# extension.net
KiCad netlist of a schematic drawn in Altium Designer
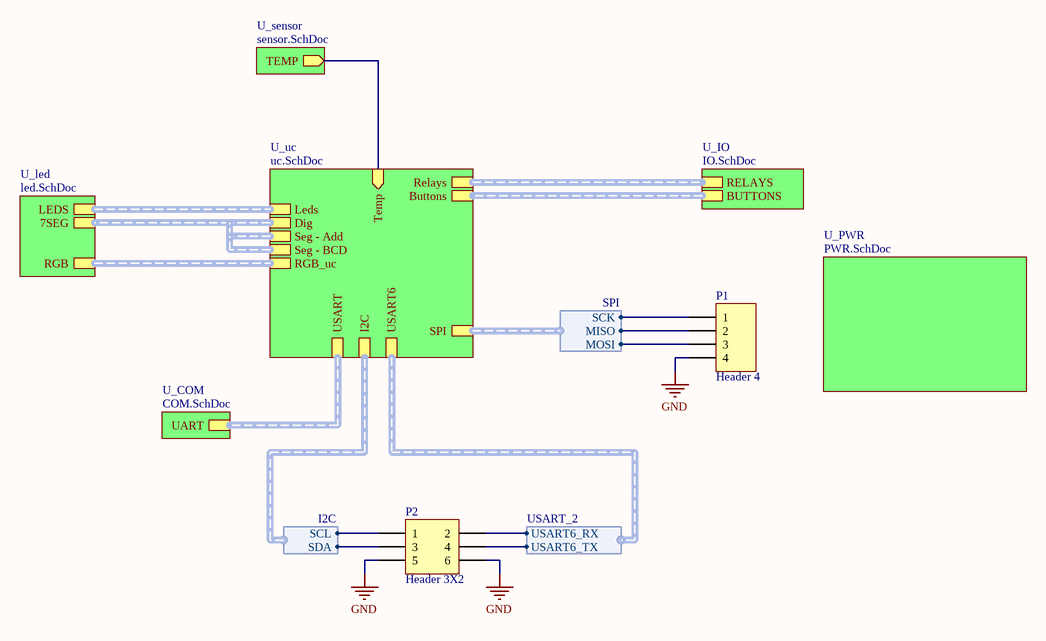
[diagram p0: extension.SchDoc]

(export (version "E")
  (design (tool "Eeschema 10.0.6"))
  (components
    (comp (ref "P1")
      (value "Header 4")
      (footprint "HDR1X4")
      (description "Header, 4-Pin")
      (libsource (lib "IDSC std connectors") (part "Header 4"))
    )
    (comp (ref "P2")
      (value "Header 3X2")
      (footprint "HDR2X3")
      (description "Header, 3-Pin, Dual row")
      (libsource (lib "IDSC std connectors") (part "Header 3X2"))
    )
  )
  (nets
    (net (code "7") (name "/MISO") (class "Default")
      (node (ref "P1") (pin "2") (pinfunction "2_2") (pintype "passive"))
    )
    (net (code "8") (name "/MOSI") (class "Default")
      (node (ref "P1") (pin "3") (pinfunction "3_3") (pintype "passive"))
    )
    (net (code "11") (name "/SCK") (class "Default")
      (node (ref "P1") (pin "1") (pinfunction "1_1") (pintype "passive"))
    )
    (net (code "12") (name "/SCL") (class "Default")
      (node (ref "P2") (pin "1") (pinfunction "1_1") (pintype "passive"))
    )
    (net (code "13") (name "/SDA") (class "Default")
      (node (ref "P2") (pin "3") (pinfunction "3_3") (pintype "passive"))
    )
    (net (code "16") (name "/USART6_RX") (class "Default")
      (node (ref "P2") (pin "2") (pinfunction "2_2") (pintype "passive"))
    )
    (net (code "17") (name "/USART6_TX") (class "Default")
      (node (ref "P2") (pin "4") (pinfunction "4_4") (pintype "passive"))
    )
    (net (code "21") (name "GND") (class "Default")
      (node (ref "P1") (pin "4") (pinfunction "4_4") (pintype "passive"))
      (node (ref "P2") (pin "5") (pinfunction "5_5") (pintype "passive"))
      (node (ref "P2") (pin "6") (pinfunction "6_6") (pintype "passive"))
    )
  )
)
